# REG_1_0.net
KiCad netlist of a schematic drawn in EAGLE
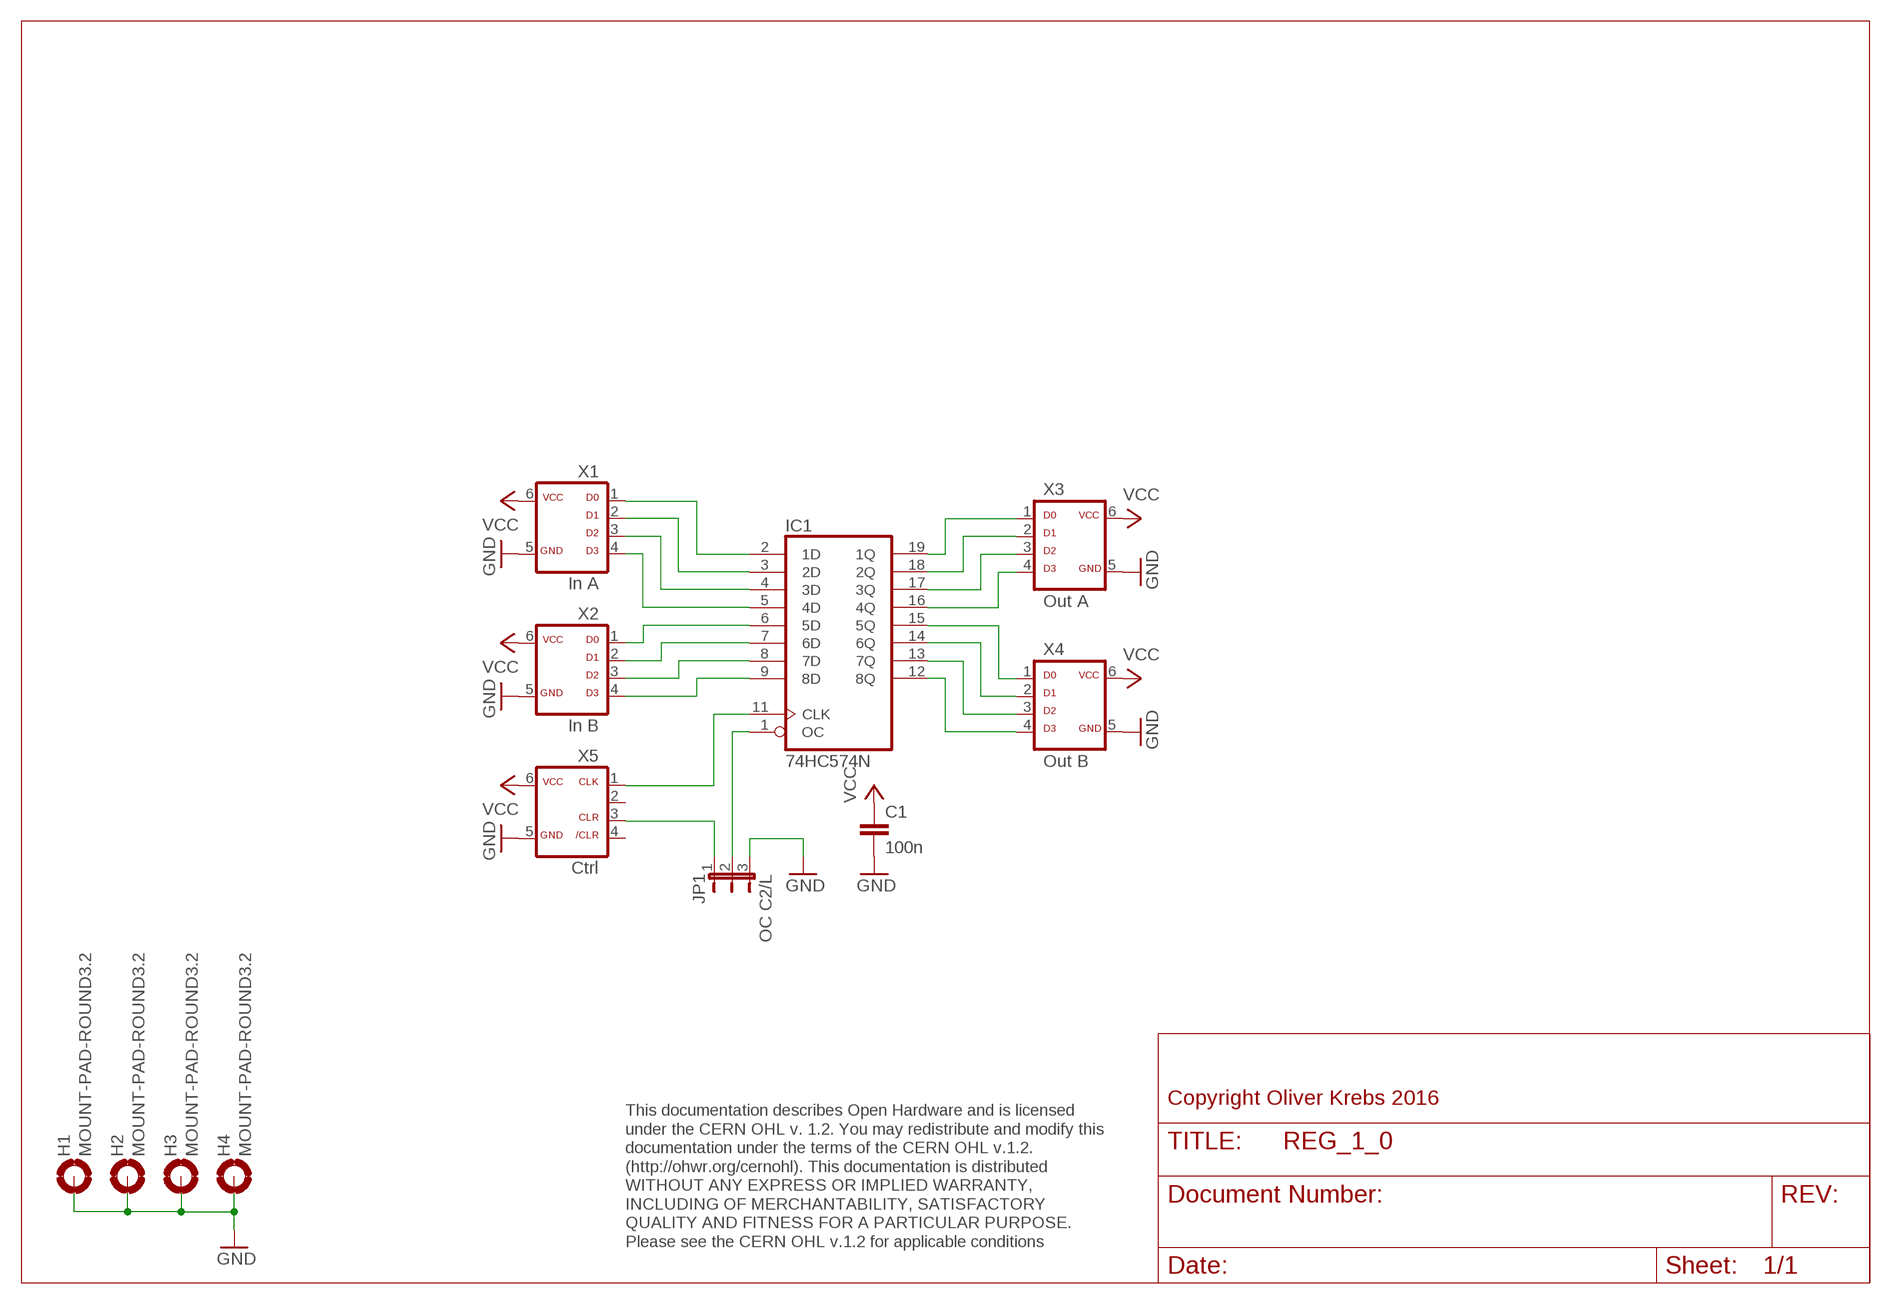
[diagram p0: schematic, sheet 1]

(export (version "E")
  (design (tool "Eeschema 10.0.6"))
  (components
    (comp (ref "C1")
      (value "100n")
      (footprint "eagle-import:C050-025X075")
      (libsource (lib "eagle-import") (part "C-EU050-025X075"))
    )
    (comp (ref "H1")
      (value "MOUNT-PAD-ROUND3.2")
      (footprint "eagle-import:3,2-PAD")
      (libsource (lib "eagle-import") (part "MOUNT-PAD-ROUND3.2"))
    )
    (comp (ref "H2")
      (value "MOUNT-PAD-ROUND3.2")
      (footprint "eagle-import:3,2-PAD")
      (libsource (lib "eagle-import") (part "MOUNT-PAD-ROUND3.2"))
    )
    (comp (ref "H3")
      (value "MOUNT-PAD-ROUND3.2")
      (footprint "eagle-import:3,2-PAD")
      (libsource (lib "eagle-import") (part "MOUNT-PAD-ROUND3.2"))
    )
    (comp (ref "H4")
      (value "MOUNT-PAD-ROUND3.2")
      (footprint "eagle-import:3,2-PAD")
      (libsource (lib "eagle-import") (part "MOUNT-PAD-ROUND3.2"))
    )
    (comp (ref "IC1")
      (value "74HC574N")
      (footprint "eagle-import:DIL20")
      (libsource (lib "eagle-import") (part "74574NHC"))
    )
    (comp (ref "JP1")
      (value "OC C2/L")
      (footprint "eagle-import:JP2")
      (libsource (lib "eagle-import") (part "JP2E"))
    )
    (comp (ref "X1")
      (value "In A")
      (footprint "eagle-import:ML-6")
      (libsource (lib "eagle-import") (part "ML6D"))
    )
    (comp (ref "X2")
      (value "In B")
      (footprint "eagle-import:ML-6")
      (libsource (lib "eagle-import") (part "ML6D"))
    )
    (comp (ref "X3")
      (value "Out A")
      (footprint "eagle-import:ML-6")
      (libsource (lib "eagle-import") (part "ML6D"))
    )
    (comp (ref "X4")
      (value "Out B")
      (footprint "eagle-import:ML-6")
      (libsource (lib "eagle-import") (part "ML6D"))
    )
    (comp (ref "X5")
      (value "Ctrl")
      (footprint "eagle-import:ML-6")
      (libsource (lib "eagle-import") (part "ML6C"))
    )
  )
  (nets
    (net (code "1") (name "GND") (class "Default")
      (node (ref "C1") (pin "2") (pinfunction "2_2") (pintype "passive"))
      (node (ref "H1") (pin "B3,2") (pinfunction "MOUNT_B3,2") (pintype "passive"))
      (node (ref "H2") (pin "B3,2") (pinfunction "MOUNT_B3,2") (pintype "passive"))
      (node (ref "H3") (pin "B3,2") (pinfunction "MOUNT_B3,2") (pintype "passive"))
      (node (ref "H4") (pin "B3,2") (pinfunction "MOUNT_B3,2") (pintype "passive"))
      (node (ref "JP1") (pin "3") (pinfunction "3_3") (pintype "passive"))
      (node (ref "X1") (pin "5") (pinfunction "5_5") (pintype "passive"))
      (node (ref "X2") (pin "5") (pinfunction "5_5") (pintype "passive"))
      (node (ref "X3") (pin "5") (pinfunction "5_5") (pintype "passive"))
      (node (ref "X4") (pin "5") (pinfunction "5_5") (pintype "passive"))
      (node (ref "X5") (pin "5") (pinfunction "5_5") (pintype "passive"))
    )
    (net (code "2") (name "Net-(IC1A-1D)") (class "Default")
      (node (ref "IC1") (pin "2") (pinfunction "1D_2") (pintype "input"))
      (node (ref "X1") (pin "1") (pinfunction "1_1") (pintype "passive"))
    )
    (net (code "3") (name "Net-(IC1A-1Q)") (class "Default")
      (node (ref "IC1") (pin "19") (pinfunction "1Q_19") (pintype "tri_state"))
      (node (ref "X3") (pin "1") (pinfunction "1_1") (pintype "passive"))
    )
    (net (code "4") (name "Net-(IC1A-2D)") (class "Default")
      (node (ref "IC1") (pin "3") (pinfunction "2D_3") (pintype "input"))
      (node (ref "X1") (pin "2") (pinfunction "2_2") (pintype "passive"))
    )
    (net (code "5") (name "Net-(IC1A-2Q)") (class "Default")
      (node (ref "IC1") (pin "18") (pinfunction "2Q_18") (pintype "tri_state"))
      (node (ref "X3") (pin "2") (pinfunction "2_2") (pintype "passive"))
    )
    (net (code "6") (name "Net-(IC1A-3D)") (class "Default")
      (node (ref "IC1") (pin "4") (pinfunction "3D_4") (pintype "input"))
      (node (ref "X1") (pin "3") (pinfunction "3_3") (pintype "passive"))
    )
    (net (code "7") (name "Net-(IC1A-3Q)") (class "Default")
      (node (ref "IC1") (pin "17") (pinfunction "3Q_17") (pintype "tri_state"))
      (node (ref "X3") (pin "3") (pinfunction "3_3") (pintype "passive"))
    )
    (net (code "8") (name "Net-(IC1A-4D)") (class "Default")
      (node (ref "IC1") (pin "5") (pinfunction "4D_5") (pintype "input"))
      (node (ref "X1") (pin "4") (pinfunction "4_4") (pintype "passive"))
    )
    (net (code "9") (name "Net-(IC1A-4Q)") (class "Default")
      (node (ref "IC1") (pin "16") (pinfunction "4Q_16") (pintype "tri_state"))
      (node (ref "X3") (pin "4") (pinfunction "4_4") (pintype "passive"))
    )
    (net (code "10") (name "Net-(IC1A-5D)") (class "Default")
      (node (ref "IC1") (pin "6") (pinfunction "5D_6") (pintype "input"))
      (node (ref "X2") (pin "1") (pinfunction "1_1") (pintype "passive"))
    )
    (net (code "11") (name "Net-(IC1A-5Q)") (class "Default")
      (node (ref "IC1") (pin "15") (pinfunction "5Q_15") (pintype "tri_state"))
      (node (ref "X4") (pin "1") (pinfunction "1_1") (pintype "passive"))
    )
    (net (code "12") (name "Net-(IC1A-6D)") (class "Default")
      (node (ref "IC1") (pin "7") (pinfunction "6D_7") (pintype "input"))
      (node (ref "X2") (pin "2") (pinfunction "2_2") (pintype "passive"))
    )
    (net (code "13") (name "Net-(IC1A-6Q)") (class "Default")
      (node (ref "IC1") (pin "14") (pinfunction "6Q_14") (pintype "tri_state"))
      (node (ref "X4") (pin "2") (pinfunction "2_2") (pintype "passive"))
    )
    (net (code "14") (name "Net-(IC1A-7D)") (class "Default")
      (node (ref "IC1") (pin "8") (pinfunction "7D_8") (pintype "input"))
      (node (ref "X2") (pin "3") (pinfunction "3_3") (pintype "passive"))
    )
    (net (code "15") (name "Net-(IC1A-7Q)") (class "Default")
      (node (ref "IC1") (pin "13") (pinfunction "7Q_13") (pintype "tri_state"))
      (node (ref "X4") (pin "3") (pinfunction "3_3") (pintype "passive"))
    )
    (net (code "16") (name "Net-(IC1A-8D)") (class "Default")
      (node (ref "IC1") (pin "9") (pinfunction "8D_9") (pintype "input"))
      (node (ref "X2") (pin "4") (pinfunction "4_4") (pintype "passive"))
    )
    (net (code "17") (name "Net-(IC1A-8Q)") (class "Default")
      (node (ref "IC1") (pin "12") (pinfunction "8Q_12") (pintype "tri_state"))
      (node (ref "X4") (pin "4") (pinfunction "4_4") (pintype "passive"))
    )
    (net (code "18") (name "Net-(IC1A-CLK)") (class "Default")
      (node (ref "IC1") (pin "11") (pinfunction "CLK_11") (pintype "input"))
      (node (ref "X5") (pin "1") (pinfunction "1_1") (pintype "passive"))
    )
    (net (code "19") (name "Net-(IC1A-OC)") (class "Default")
      (node (ref "IC1") (pin "1") (pinfunction "OC_1") (pintype "input"))
      (node (ref "JP1") (pin "2") (pinfunction "2_2") (pintype "passive"))
    )
    (net (code "20") (name "Net-(JP1-Pad1)") (class "Default")
      (node (ref "JP1") (pin "1") (pinfunction "1_1") (pintype "passive"))
      (node (ref "X5") (pin "3") (pinfunction "3_3") (pintype "passive"))
    )
    (net (code "21") (name "VCC") (class "Default")
      (node (ref "C1") (pin "1") (pinfunction "1_1") (pintype "passive"))
      (node (ref "X1") (pin "6") (pinfunction "6_6") (pintype "passive"))
      (node (ref "X2") (pin "6") (pinfunction "6_6") (pintype "passive"))
      (node (ref "X3") (pin "6") (pinfunction "6_6") (pintype "passive"))
      (node (ref "X4") (pin "6") (pinfunction "6_6") (pintype "passive"))
      (node (ref "X5") (pin "6") (pinfunction "6_6") (pintype "passive"))
    )
    (net (code "22") (name "unconnected-(X5-Pad2)") (class "Default")
      (node (ref "X5") (pin "2") (pinfunction "2_2") (pintype "passive"))
    )
    (net (code "23") (name "unconnected-(X5-Pad4)") (class "Default")
      (node (ref "X5") (pin "4") (pinfunction "4_4") (pintype "passive"))
    )
  )
)
